# photonAlarm5.net
KiCad netlist of a schematic drawn in EAGLE
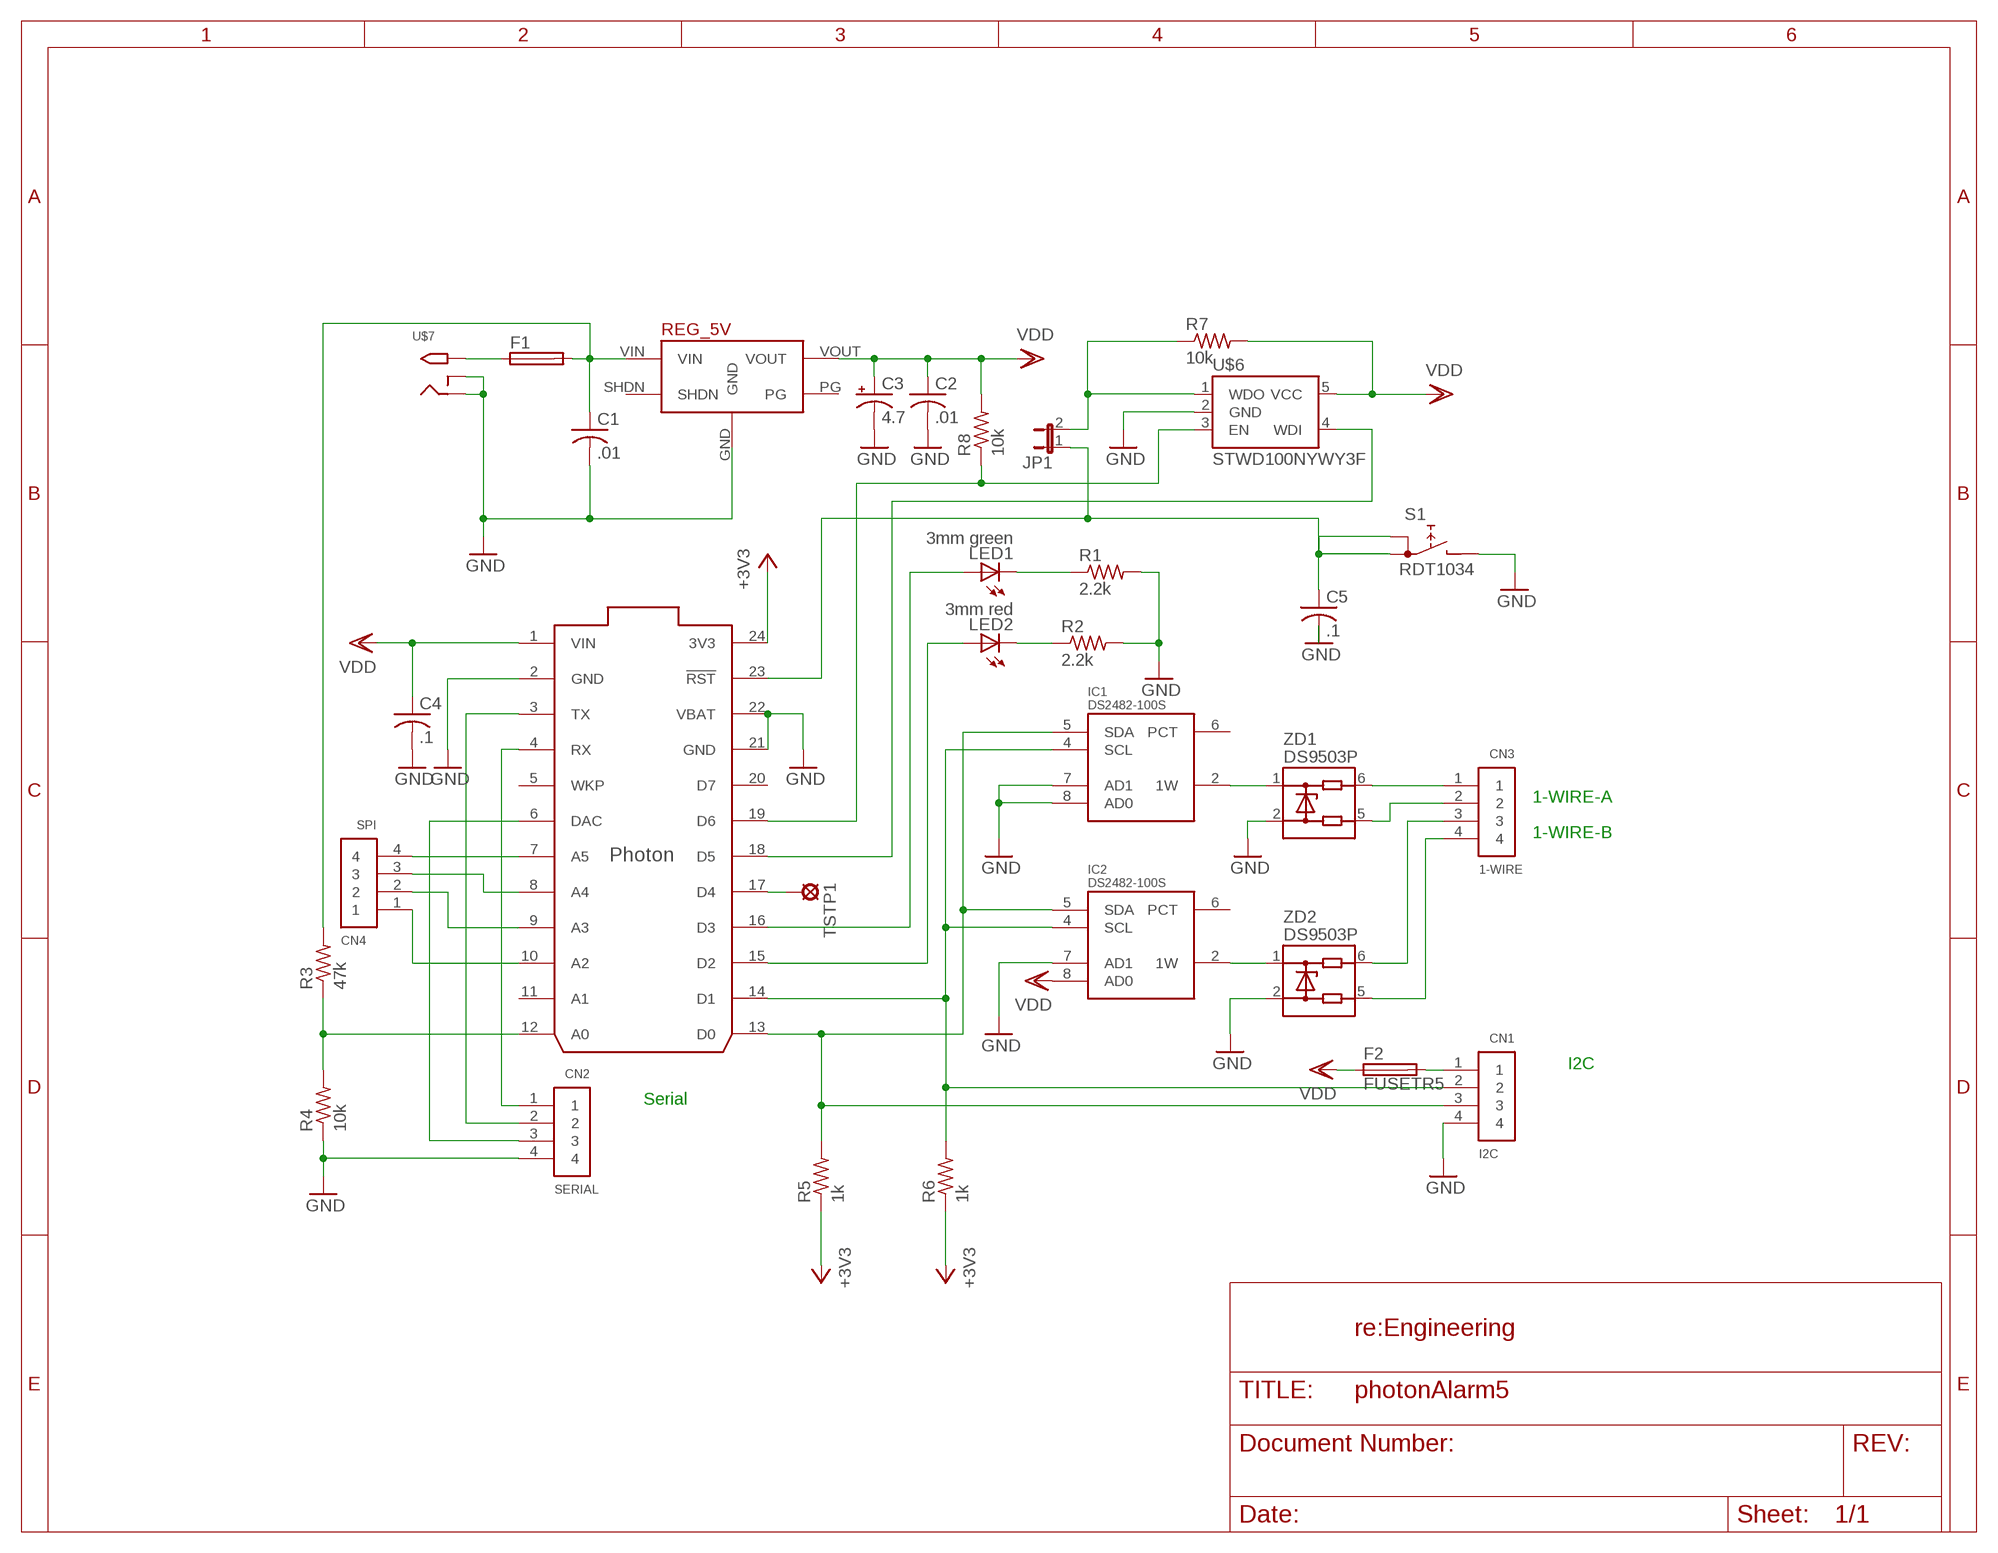
[diagram p0: schematic, sheet 1]

(export (version "E")
  (design (tool "Eeschema 10.0.6"))
  (components
    (comp (ref "C1")
      (value ".01")
      (footprint "eagle-import:C0805")
      (libsource (lib "eagle-import") (part "C-USC0805"))
    )
    (comp (ref "C2")
      (value ".01")
      (footprint "eagle-import:C0805")
      (libsource (lib "eagle-import") (part "C-USC0805"))
    )
    (comp (ref "C3")
      (value "4.7")
      (footprint "eagle-import:E2,5-6E")
      (libsource (lib "eagle-import") (part "CPOL-USE2,5-6E"))
    )
    (comp (ref "C4")
      (value ".1")
      (footprint "eagle-import:C0805")
      (libsource (lib "eagle-import") (part "C-USC0805"))
    )
    (comp (ref "C5")
      (value ".1")
      (footprint "eagle-import:C0805")
      (libsource (lib "eagle-import") (part "C-USC0805"))
    )
    (comp (ref "CN1")
      (value "I2C")
      (footprint "eagle-import:1X04-BIG")
      (libsource (lib "eagle-import") (part "1X4-BIG"))
    )
    (comp (ref "CN2")
      (value "SERIAL")
      (footprint "eagle-import:1X04-BIG")
      (libsource (lib "eagle-import") (part "1X4-BIG"))
    )
    (comp (ref "CN3")
      (value "1-WIRE")
      (footprint "eagle-import:1X04-BIG")
      (libsource (lib "eagle-import") (part "1X4-BIG"))
    )
    (comp (ref "CN4")
      (value "SPI")
      (footprint "eagle-import:1X04-BIG")
      (libsource (lib "eagle-import") (part "1X4-BIG"))
    )
    (comp (ref "F1")
      (value "PICOFUSE")
      (footprint "eagle-import:PICOFUSE")
      (libsource (lib "eagle-import") (part "PICOFUSE"))
    )
    (comp (ref "F2")
      (value "FUSETR5")
      (footprint "eagle-import:TR5")
      (libsource (lib "eagle-import") (part "FUSETR5"))
    )
    (comp (ref "IC1")
      (value "DS2482-100S")
      (footprint "eagle-import:SO08")
      (libsource (lib "eagle-import") (part "DS2482-100S"))
    )
    (comp (ref "IC2")
      (value "DS2482-100S")
      (footprint "eagle-import:SO08")
      (libsource (lib "eagle-import") (part "DS2482-100S"))
    )
    (comp (ref "JP1")
      (value "JP1E")
      (footprint "eagle-import:JP1")
      (libsource (lib "eagle-import") (part "JP1E"))
    )
    (comp (ref "LED1")
      (value "3mm green")
      (footprint "eagle-import:LED5MM")
      (libsource (lib "eagle-import") (part "LED5MM"))
    )
    (comp (ref "LED2")
      (value "3mm red")
      (footprint "eagle-import:LED5MM")
      (libsource (lib "eagle-import") (part "LED5MM"))
    )
    (comp (ref "R1")
      (value "2.2k")
      (footprint "eagle-import:R1206")
      (libsource (lib "eagle-import") (part "R-US_R1206"))
    )
    (comp (ref "R2")
      (value "2.2k")
      (footprint "eagle-import:R1206")
      (libsource (lib "eagle-import") (part "R-US_R1206"))
    )
    (comp (ref "R3")
      (value "47k")
      (footprint "eagle-import:R1206")
      (libsource (lib "eagle-import") (part "R-US_R1206"))
    )
    (comp (ref "R4")
      (value "10k")
      (footprint "eagle-import:R1206")
      (libsource (lib "eagle-import") (part "R-US_R1206"))
    )
    (comp (ref "R5")
      (value "1k")
      (footprint "eagle-import:R1206")
      (libsource (lib "eagle-import") (part "R-US_R1206"))
    )
    (comp (ref "R6")
      (value "1k")
      (footprint "eagle-import:R1206")
      (libsource (lib "eagle-import") (part "R-US_R1206"))
    )
    (comp (ref "R7")
      (value "10k")
      (footprint "eagle-import:R1206")
      (libsource (lib "eagle-import") (part "R-US_R1206"))
    )
    (comp (ref "R8")
      (value "10k")
      (footprint "eagle-import:R1206")
      (libsource (lib "eagle-import") (part "R-US_R1206"))
    )
    (comp (ref "REG_5V")
      (value "5V_D24V10FAD24V10F5MIR")
      (footprint "eagle-import:5V_D24V10F5")
      (libsource (lib "eagle-import") (part "5V_D24V10FAD24V10F5MIR"))
    )
    (comp (ref "S1")
      (value "RDT1034")
      (footprint "eagle-import:RDT1034")
      (libsource (lib "eagle-import") (part "RDT1034"))
    )
    (comp (ref "TSTP1")
      (value "LSP10")
      (footprint "eagle-import:LSP10")
      (libsource (lib "eagle-import") (part "LSP10"))
    )
    (comp (ref "U$1")
      (value "PHOTON_WITH_HEADERS")
      (footprint "eagle-import:PHOTON")
      (libsource (lib "eagle-import") (part "PHOTON_WITH_HEADERS"))
    )
    (comp (ref "U$6")
      (value "STWD100NYWY3F")
      (footprint "eagle-import:SOT23-5")
      (libsource (lib "eagle-import") (part "STWD100NYWY3F"))
    )
    (comp (ref "U$7")
      (value "2.1MMJACKSMT")
      (footprint "eagle-import:DCJACK_2MM_SMT")
      (libsource (lib "eagle-import") (part "2.1MMJACKSMT"))
    )
    (comp (ref "ZD1")
      (value "DS9503P")
      (footprint "eagle-import:TSOC6")
      (libsource (lib "eagle-import") (part "DS9503P"))
    )
    (comp (ref "ZD2")
      (value "DS9503P")
      (footprint "eagle-import:TSOC6")
      (libsource (lib "eagle-import") (part "DS9503P"))
    )
  )
  (nets
    (net (code "1") (name "+3V3") (class "Default")
      (node (ref "R5") (pin "1") (pinfunction "1_1") (pintype "passive"))
      (node (ref "R6") (pin "1") (pinfunction "1_1") (pintype "passive"))
      (node (ref "U$1") (pin "24") (pinfunction "3V3_24") (pintype "power_in"))
    )
    (net (code "2") (name "GND") (class "Default")
      (node (ref "C1") (pin "2") (pinfunction "2_2") (pintype "passive"))
      (node (ref "C2") (pin "2") (pinfunction "2_2") (pintype "passive"))
      (node (ref "C3") (pin "-") (pinfunction "-_-") (pintype "passive"))
      (node (ref "C4") (pin "2") (pinfunction "2_2") (pintype "passive"))
      (node (ref "C5") (pin "2") (pinfunction "2_2") (pintype "passive"))
      (node (ref "CN1") (pin "4") (pinfunction "4_4") (pintype "bidirectional"))
      (node (ref "CN2") (pin "4") (pinfunction "4_4") (pintype "bidirectional"))
      (node (ref "IC1") (pin "7") (pinfunction "AD1_7") (pintype "input"))
      (node (ref "IC1") (pin "8") (pinfunction "AD0_8") (pintype "input"))
      (node (ref "IC2") (pin "7") (pinfunction "AD1_7") (pintype "input"))
      (node (ref "R1") (pin "2") (pinfunction "2_2") (pintype "passive"))
      (node (ref "R2") (pin "2") (pinfunction "2_2") (pintype "passive"))
      (node (ref "R4") (pin "1") (pinfunction "1_1") (pintype "passive"))
      (node (ref "REG_5V") (pin "GND") (pinfunction "GND_GND") (pintype "bidirectional"))
      (node (ref "S1") (pin "B") (pinfunction "B_B") (pintype "passive"))
      (node (ref "U$1") (pin "2") (pinfunction "GND_2") (pintype "power_in"))
      (node (ref "U$1") (pin "21") (pinfunction "GND_21") (pintype "power_in"))
      (node (ref "U$1") (pin "22") (pinfunction "VBAT_22") (pintype "power_in"))
      (node (ref "U$6") (pin "2") (pinfunction "GND_2") (pintype "bidirectional"))
      (node (ref "U$7") (pin "GND") (pinfunction "RING_GND") (pintype "bidirectional"))
      (node (ref "U$7") (pin "GNDBREAK") (pinfunction "RING_SW_GNDBREAK") (pintype "bidirectional"))
      (node (ref "ZD1") (pin "2") (pinfunction "P$2_2") (pintype "passive"))
      (node (ref "ZD2") (pin "2") (pinfunction "P$2_2") (pintype "passive"))
    )
    (net (code "3") (name "Net-(C1-Pad1)") (class "Default")
      (node (ref "C1") (pin "1") (pinfunction "1_1") (pintype "passive"))
      (node (ref "F1") (pin "2") (pinfunction "2_2") (pintype "passive"))
      (node (ref "R3") (pin "2") (pinfunction "2_2") (pintype "passive"))
      (node (ref "REG_5V") (pin "VIN") (pinfunction "VIN_VIN") (pintype "bidirectional"))
    )
    (net (code "4") (name "Net-(CN1-Pad1)") (class "Default")
      (node (ref "CN1") (pin "1") (pinfunction "1_1") (pintype "bidirectional"))
      (node (ref "F2") (pin "2") (pinfunction "2_2") (pintype "passive"))
    )
    (net (code "5") (name "Net-(IC1A-1W)") (class "Default")
      (node (ref "IC1") (pin "2") (pinfunction "1W_2") (pintype "open_collector"))
      (node (ref "ZD1") (pin "1") (pinfunction "P$1_1") (pintype "passive"))
    )
    (net (code "6") (name "Net-(IC1A-SCL)") (class "Default")
      (node (ref "CN1") (pin "2") (pinfunction "2_2") (pintype "bidirectional"))
      (node (ref "IC1") (pin "4") (pinfunction "SCL_4") (pintype "input"))
      (node (ref "IC2") (pin "4") (pinfunction "SCL_4") (pintype "input"))
      (node (ref "R6") (pin "2") (pinfunction "2_2") (pintype "passive"))
      (node (ref "U$1") (pin "14") (pinfunction "D1_14") (pintype "bidirectional"))
    )
    (net (code "7") (name "Net-(IC1A-SDA)") (class "Default")
      (node (ref "CN1") (pin "3") (pinfunction "3_3") (pintype "bidirectional"))
      (node (ref "IC1") (pin "5") (pinfunction "SDA_5") (pintype "bidirectional"))
      (node (ref "IC2") (pin "5") (pinfunction "SDA_5") (pintype "bidirectional"))
      (node (ref "R5") (pin "2") (pinfunction "2_2") (pintype "passive"))
      (node (ref "U$1") (pin "13") (pinfunction "D0_13") (pintype "bidirectional"))
    )
    (net (code "8") (name "Net-(IC2A-1W)") (class "Default")
      (node (ref "IC2") (pin "2") (pinfunction "1W_2") (pintype "open_collector"))
      (node (ref "ZD2") (pin "1") (pinfunction "P$1_1") (pintype "passive"))
    )
    (net (code "9") (name "Net-(LED1-C)") (class "Default")
      (node (ref "LED1") (pin "K") (pinfunction "C_K") (pintype "passive"))
      (node (ref "R1") (pin "1") (pinfunction "1_1") (pintype "passive"))
    )
    (net (code "10") (name "Net-(LED2-C)") (class "Default")
      (node (ref "LED2") (pin "K") (pinfunction "C_K") (pintype "passive"))
      (node (ref "R2") (pin "1") (pinfunction "1_1") (pintype "passive"))
    )
    (net (code "11") (name "Net-(U$1-A0)") (class "Default")
      (node (ref "R3") (pin "1") (pinfunction "1_1") (pintype "passive"))
      (node (ref "R4") (pin "2") (pinfunction "2_2") (pintype "passive"))
      (node (ref "U$1") (pin "12") (pinfunction "A0_12") (pintype "bidirectional"))
    )
    (net (code "12") (name "Net-(U$1-A2)") (class "Default")
      (node (ref "CN4") (pin "1") (pinfunction "1_1") (pintype "bidirectional"))
      (node (ref "U$1") (pin "10") (pinfunction "A2_10") (pintype "bidirectional"))
    )
    (net (code "13") (name "Net-(U$1-A3)") (class "Default")
      (node (ref "CN4") (pin "2") (pinfunction "2_2") (pintype "bidirectional"))
      (node (ref "U$1") (pin "9") (pinfunction "A3_9") (pintype "bidirectional"))
    )
    (net (code "14") (name "Net-(U$1-A4)") (class "Default")
      (node (ref "CN4") (pin "3") (pinfunction "3_3") (pintype "bidirectional"))
      (node (ref "U$1") (pin "8") (pinfunction "A4_8") (pintype "bidirectional"))
    )
    (net (code "15") (name "Net-(U$1-A5)") (class "Default")
      (node (ref "CN4") (pin "4") (pinfunction "4_4") (pintype "bidirectional"))
      (node (ref "U$1") (pin "7") (pinfunction "A5_7") (pintype "bidirectional"))
    )
    (net (code "16") (name "Net-(U$1-D2)") (class "Default")
      (node (ref "LED2") (pin "A") (pinfunction "A_A") (pintype "passive"))
      (node (ref "U$1") (pin "15") (pinfunction "D2_15") (pintype "bidirectional"))
    )
    (net (code "17") (name "Net-(U$1-D3)") (class "Default")
      (node (ref "LED1") (pin "A") (pinfunction "A_A") (pintype "passive"))
      (node (ref "U$1") (pin "16") (pinfunction "D3_16") (pintype "bidirectional"))
    )
    (net (code "18") (name "Net-(U$1-D4)") (class "Default")
      (node (ref "TSTP1") (pin "MP") (pinfunction "MP_MP") (pintype "passive"))
      (node (ref "U$1") (pin "17") (pinfunction "D4_17") (pintype "bidirectional"))
    )
    (net (code "19") (name "Net-(U$1-D5)") (class "Default")
      (node (ref "U$1") (pin "18") (pinfunction "D5_18") (pintype "bidirectional"))
      (node (ref "U$6") (pin "4") (pinfunction "WDI_4") (pintype "bidirectional"))
    )
    (net (code "20") (name "Net-(U$1-D6)") (class "Default")
      (node (ref "R8") (pin "1") (pinfunction "1_1") (pintype "passive"))
      (node (ref "U$1") (pin "19") (pinfunction "D6_19") (pintype "bidirectional"))
      (node (ref "U$6") (pin "3") (pinfunction "EN_3") (pintype "bidirectional"))
    )
    (net (code "21") (name "Net-(U$1-DAC)") (class "Default")
      (node (ref "CN2") (pin "3") (pinfunction "3_3") (pintype "bidirectional"))
      (node (ref "U$1") (pin "6") (pinfunction "DAC_6") (pintype "bidirectional"))
    )
    (net (code "22") (name "Net-(U$1-RX)") (class "Default")
      (node (ref "CN2") (pin "1") (pinfunction "1_1") (pintype "bidirectional"))
      (node (ref "U$1") (pin "4") (pinfunction "RX_4") (pintype "bidirectional"))
    )
    (net (code "23") (name "Net-(U$1-TX)") (class "Default")
      (node (ref "CN2") (pin "2") (pinfunction "2_2") (pintype "bidirectional"))
      (node (ref "U$1") (pin "3") (pinfunction "TX_3") (pintype "bidirectional"))
    )
    (net (code "24") (name "Net-(U$1-~{RST})") (class "Default")
      (node (ref "C5") (pin "1") (pinfunction "1_1") (pintype "passive"))
      (node (ref "JP1") (pin "1") (pinfunction "1_1") (pintype "passive"))
      (node (ref "S1") (pin "A") (pinfunction "A_A") (pintype "passive"))
      (node (ref "S1") (pin "A1") (pinfunction "A1_A1") (pintype "passive"))
      (node (ref "U$1") (pin "23") (pinfunction "~{RST}_23") (pintype "bidirectional"))
    )
    (net (code "25") (name "Net-(U$6-WDO)") (class "Default")
      (node (ref "JP1") (pin "2") (pinfunction "2_2") (pintype "passive"))
      (node (ref "R7") (pin "1") (pinfunction "1_1") (pintype "passive"))
      (node (ref "U$6") (pin "1") (pinfunction "WDO_1") (pintype "output"))
    )
    (net (code "26") (name "Net-(U$7-TIP)") (class "Default")
      (node (ref "F1") (pin "1") (pinfunction "1_1") (pintype "passive"))
      (node (ref "U$7") (pin "PWR2") (pinfunction "TIP_PWR2") (pintype "bidirectional"))
    )
    (net (code "27") (name "Net-(ZD1-P$3)") (class "Default")
      (node (ref "CN3") (pin "2") (pinfunction "2_2") (pintype "bidirectional"))
      (node (ref "ZD1") (pin "5") (pinfunction "P$3_5") (pintype "passive"))
    )
    (net (code "28") (name "Net-(ZD1-P$4)") (class "Default")
      (node (ref "CN3") (pin "1") (pinfunction "1_1") (pintype "bidirectional"))
      (node (ref "ZD1") (pin "6") (pinfunction "P$4_6") (pintype "passive"))
    )
    (net (code "29") (name "Net-(ZD2-P$3)") (class "Default")
      (node (ref "CN3") (pin "4") (pinfunction "4_4") (pintype "bidirectional"))
      (node (ref "ZD2") (pin "5") (pinfunction "P$3_5") (pintype "passive"))
    )
    (net (code "30") (name "Net-(ZD2-P$4)") (class "Default")
      (node (ref "CN3") (pin "3") (pinfunction "3_3") (pintype "bidirectional"))
      (node (ref "ZD2") (pin "6") (pinfunction "P$4_6") (pintype "passive"))
    )
    (net (code "31") (name "VDD") (class "Default")
      (node (ref "C2") (pin "1") (pinfunction "1_1") (pintype "passive"))
      (node (ref "C3") (pin "+") (pinfunction "+_+") (pintype "passive"))
      (node (ref "C4") (pin "1") (pinfunction "1_1") (pintype "passive"))
      (node (ref "F2") (pin "1") (pinfunction "1_1") (pintype "passive"))
      (node (ref "IC2") (pin "8") (pinfunction "AD0_8") (pintype "input"))
      (node (ref "R7") (pin "2") (pinfunction "2_2") (pintype "passive"))
      (node (ref "R8") (pin "2") (pinfunction "2_2") (pintype "passive"))
      (node (ref "REG_5V") (pin "VOUT") (pinfunction "VOUT_VOUT") (pintype "bidirectional"))
      (node (ref "U$1") (pin "1") (pinfunction "VIN_1") (pintype "power_in"))
      (node (ref "U$6") (pin "5") (pinfunction "VCC_5") (pintype "bidirectional"))
    )
    (net (code "32") (name "unconnected-(IC1A-PCT-Pad6)") (class "Default")
      (node (ref "IC1") (pin "6") (pinfunction "PCT_6") (pintype "output"))
    )
    (net (code "33") (name "unconnected-(IC2A-PCT-Pad6)") (class "Default")
      (node (ref "IC2") (pin "6") (pinfunction "PCT_6") (pintype "output"))
    )
    (net (code "34") (name "unconnected-(REG_5V-PadPG)") (class "Default")
      (node (ref "REG_5V") (pin "PG") (pinfunction "PG_PG") (pintype "bidirectional"))
    )
    (net (code "35") (name "unconnected-(REG_5V-PadSHDN)") (class "Default")
      (node (ref "REG_5V") (pin "SHDN") (pinfunction "SHDN_SHDN") (pintype "bidirectional"))
    )
    (net (code "36") (name "unconnected-(U$1-A1-Pad11)") (class "Default")
      (node (ref "U$1") (pin "11") (pinfunction "A1_11") (pintype "bidirectional"))
    )
    (net (code "37") (name "unconnected-(U$1-D7-Pad20)") (class "Default")
      (node (ref "U$1") (pin "20") (pinfunction "D7_20") (pintype "bidirectional"))
    )
    (net (code "38") (name "unconnected-(U$1-WKP-Pad5)") (class "Default")
      (node (ref "U$1") (pin "5") (pinfunction "WKP_5") (pintype "bidirectional"))
    )
  )
)
